# blink1mk3_003.net
KiCad netlist of a schematic drawn in EAGLE
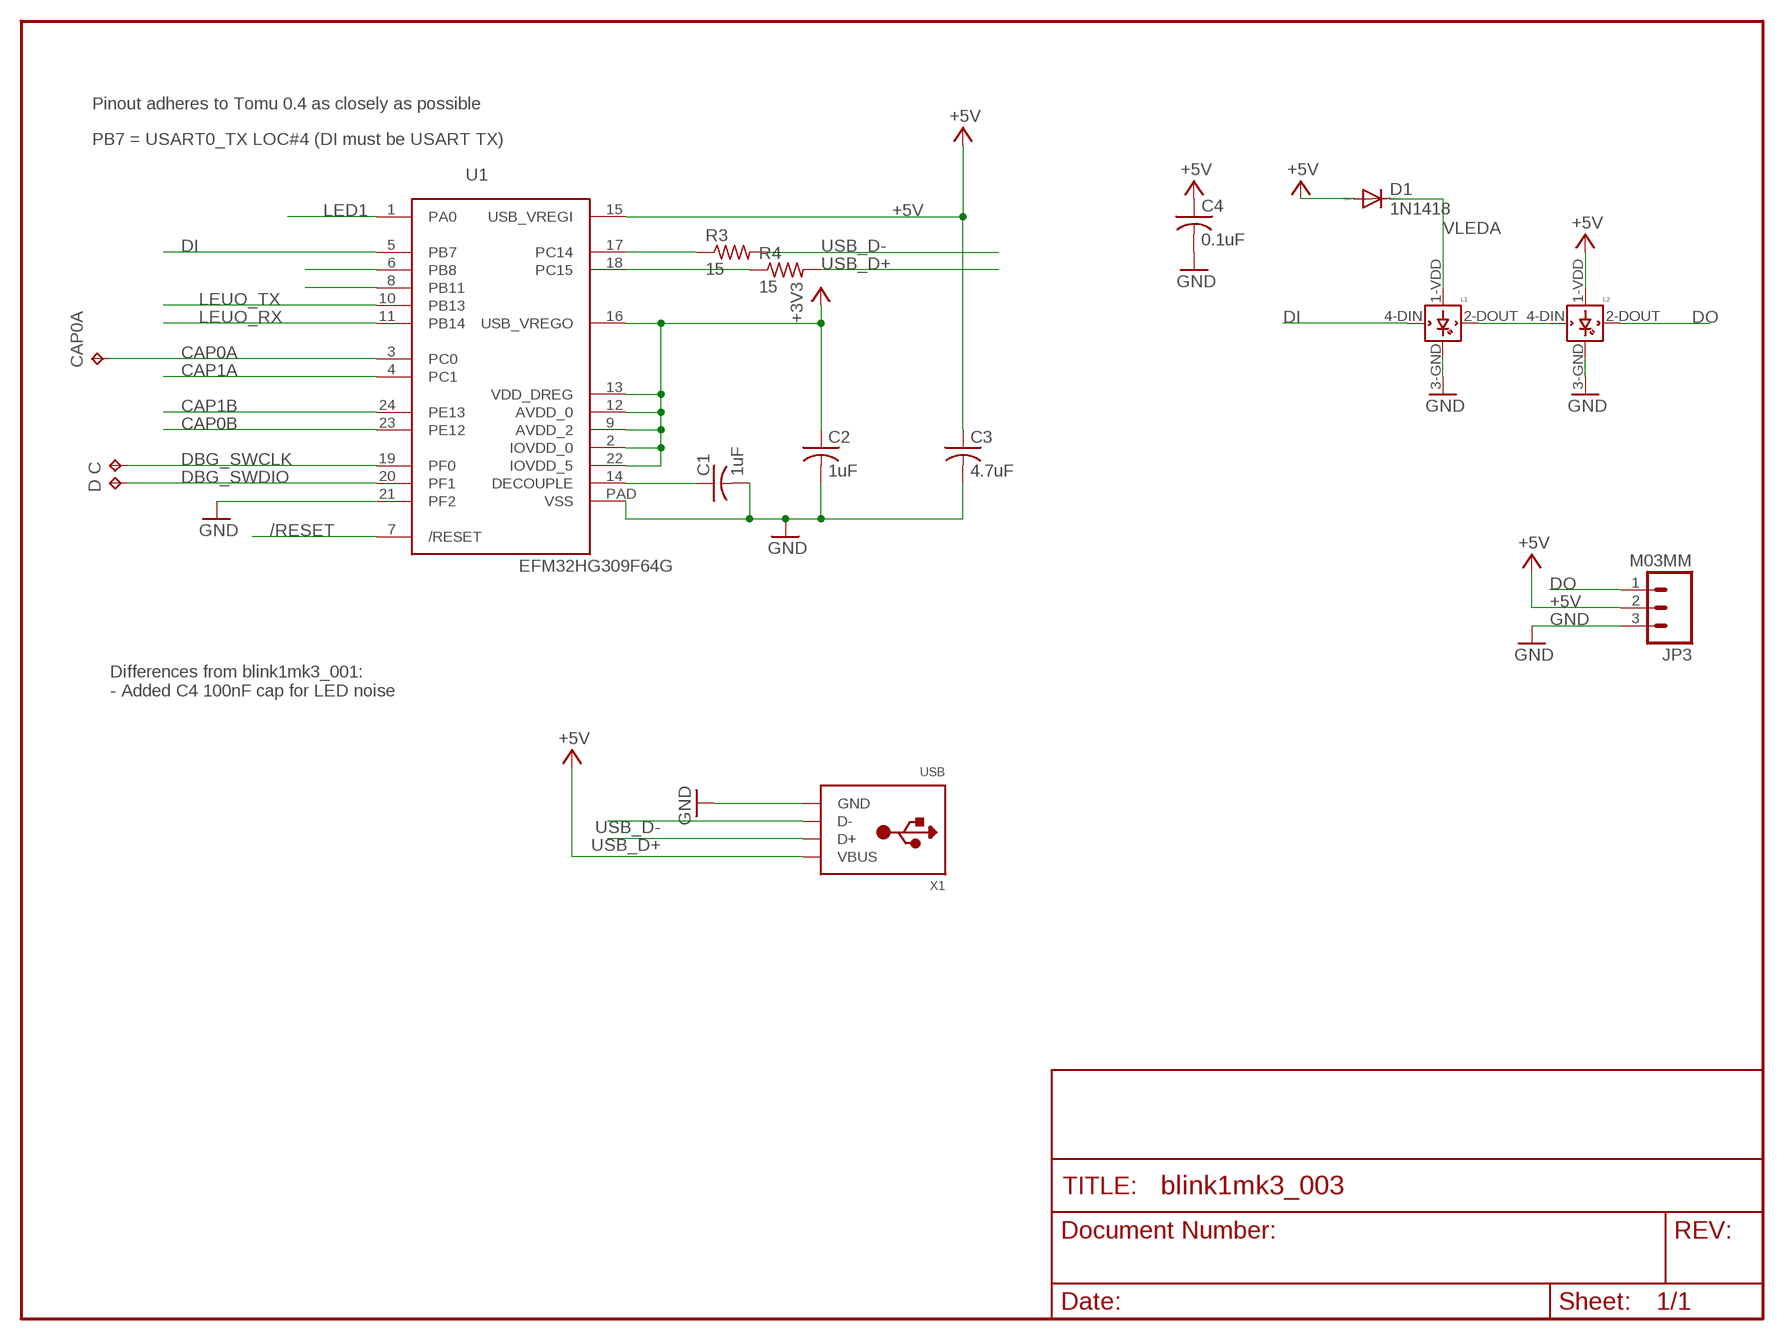
[diagram p0: schematic, sheet 1]

(export (version "E")
  (design (tool "Eeschema 10.0.6"))
  (components
    (comp (ref "C")
      (value "TPTP10R")
      (footprint "eagle-import:TP10R")
      (libsource (lib "eagle-import") (part "TPTP10R"))
    )
    (comp (ref "C1")
      (value "1uF")
      (footprint "eagle-import:C0402")
      (libsource (lib "eagle-import") (part "C-USC0402"))
    )
    (comp (ref "C2")
      (value "1uF")
      (footprint "eagle-import:C0402")
      (libsource (lib "eagle-import") (part "C-USC0402"))
    )
    (comp (ref "C3")
      (value "4.7uF")
      (footprint "eagle-import:C0402")
      (libsource (lib "eagle-import") (part "C-USC0402"))
    )
    (comp (ref "C4")
      (value "0.1uF")
      (footprint "eagle-import:C0402")
      (libsource (lib "eagle-import") (part "C-USC0402"))
    )
    (comp (ref "CAP0A")
      (value "TPTP10R")
      (footprint "eagle-import:TP10R")
      (libsource (lib "eagle-import") (part "TPTP10R"))
    )
    (comp (ref "D")
      (value "TPTP10R")
      (footprint "eagle-import:TP10R")
      (libsource (lib "eagle-import") (part "TPTP10R"))
    )
    (comp (ref "D1")
      (value "1N1418")
      (footprint "eagle-import:SOD523")
      (libsource (lib "eagle-import") (part "DIODE-SOD523"))
    )
    (comp (ref "JP3")
      (value "M03MM")
      (footprint "eagle-import:1X03-1.5MM")
      (libsource (lib "eagle-import") (part "M03MM"))
    )
    (comp (ref "L1")
      (value "WS2812B")
      (footprint "eagle-import:WS2812B")
      (libsource (lib "eagle-import") (part "WS2812B"))
    )
    (comp (ref "L2")
      (value "WS2812B")
      (footprint "eagle-import:WS2812B")
      (libsource (lib "eagle-import") (part "WS2812B"))
    )
    (comp (ref "R3")
      (value "15")
      (footprint "eagle-import:R0402")
      (libsource (lib "eagle-import") (part "R-US_R0402"))
    )
    (comp (ref "R4")
      (value "15")
      (footprint "eagle-import:R0402")
      (libsource (lib "eagle-import") (part "R-US_R0402"))
    )
    (comp (ref "U1")
      (value "EFM32HG309F64G")
      (footprint "eagle-import:QFN24PAD")
      (libsource (lib "eagle-import") (part "EFM32HG309F64G"))
    )
    (comp (ref "X1")
      (value "USB")
      (footprint "eagle-import:MOLEX-48037-1000")
      (libsource (lib "eagle-import") (part "USB"))
    )
  )
  (nets
    (net (code "1") (name "+3V3") (class "Default")
      (node (ref "C2") (pin "1") (pinfunction "1_1") (pintype "passive"))
      (node (ref "U1") (pin "12") (pinfunction "AVDD_0_12") (pintype "bidirectional"))
      (node (ref "U1") (pin "13") (pinfunction "VDD_DREG_13") (pintype "bidirectional"))
      (node (ref "U1") (pin "16") (pinfunction "USB_VREGO_16") (pintype "bidirectional"))
      (node (ref "U1") (pin "2") (pinfunction "IOVDD_0_2") (pintype "bidirectional"))
      (node (ref "U1") (pin "22") (pinfunction "IOVDD_5_22") (pintype "bidirectional"))
      (node (ref "U1") (pin "9") (pinfunction "AVDD_2_9") (pintype "bidirectional"))
    )
    (net (code "2") (name "+5V") (class "Default")
      (node (ref "C3") (pin "1") (pinfunction "1_1") (pintype "passive"))
      (node (ref "C4") (pin "1") (pinfunction "1_1") (pintype "passive"))
      (node (ref "D1") (pin "A") (pinfunction "A_A") (pintype "passive"))
      (node (ref "JP3") (pin "2") (pinfunction "2_2") (pintype "passive"))
      (node (ref "L2") (pin "1-VDD") (pinfunction "VDD_1-VDD") (pintype "bidirectional"))
      (node (ref "U1") (pin "15") (pinfunction "USB_VREGI_15") (pintype "bidirectional"))
      (node (ref "X1") (pin "1") (pinfunction "VBUS_1") (pintype "power_in"))
    )
    (net (code "3") (name "/CAP0A") (class "Default")
      (node (ref "CAP0A") (pin "TP") (pinfunction "TP_TP") (pintype "input"))
      (node (ref "U1") (pin "3") (pinfunction "PC0_3") (pintype "bidirectional"))
    )
    (net (code "4") (name "/CAP0B") (class "Default")
      (node (ref "U1") (pin "23") (pinfunction "PE12_23") (pintype "bidirectional"))
    )
    (net (code "5") (name "/CAP1A") (class "Default")
      (node (ref "U1") (pin "4") (pinfunction "PC1_4") (pintype "bidirectional"))
    )
    (net (code "6") (name "/CAP1B") (class "Default")
      (node (ref "U1") (pin "24") (pinfunction "PE13_24") (pintype "bidirectional"))
    )
    (net (code "7") (name "/DBG_SWCLK") (class "Default")
      (node (ref "C") (pin "TP") (pinfunction "TP_TP") (pintype "input"))
      (node (ref "U1") (pin "19") (pinfunction "PF0_19") (pintype "bidirectional"))
    )
    (net (code "8") (name "/DBG_SWDIO") (class "Default")
      (node (ref "D") (pin "TP") (pinfunction "TP_TP") (pintype "input"))
      (node (ref "U1") (pin "20") (pinfunction "PF1_20") (pintype "bidirectional"))
    )
    (net (code "9") (name "/DI") (class "Default")
      (node (ref "L1") (pin "4-DIN") (pinfunction "DIN_4-DIN") (pintype "input"))
      (node (ref "U1") (pin "5") (pinfunction "PB7_5") (pintype "bidirectional"))
    )
    (net (code "10") (name "/DO") (class "Default")
      (node (ref "JP3") (pin "1") (pinfunction "1_1") (pintype "passive"))
      (node (ref "L2") (pin "2-DOUT") (pinfunction "DOUT_2-DOUT") (pintype "output"))
    )
    (net (code "11") (name "/LED1") (class "Default")
      (node (ref "U1") (pin "1") (pinfunction "PA0_1") (pintype "bidirectional"))
    )
    (net (code "12") (name "/LEUO_RX") (class "Default")
      (node (ref "U1") (pin "11") (pinfunction "PB14_11") (pintype "bidirectional"))
    )
    (net (code "13") (name "/LEUO_TX") (class "Default")
      (node (ref "U1") (pin "10") (pinfunction "PB13_10") (pintype "bidirectional"))
    )
    (net (code "14") (name "/USB_D+") (class "Default")
      (node (ref "R4") (pin "2") (pinfunction "2_2") (pintype "passive"))
      (node (ref "X1") (pin "3") (pinfunction "D+_3") (pintype "bidirectional"))
    )
    (net (code "15") (name "/USB_D-") (class "Default")
      (node (ref "R3") (pin "2") (pinfunction "2_2") (pintype "passive"))
      (node (ref "X1") (pin "2") (pinfunction "D-_2") (pintype "bidirectional"))
    )
    (net (code "16") (name "/VLEDA") (class "Default")
      (node (ref "D1") (pin "C") (pinfunction "C_C") (pintype "passive"))
      (node (ref "L1") (pin "1-VDD") (pinfunction "VDD_1-VDD") (pintype "bidirectional"))
    )
    (net (code "17") (name "/{slash}RESET") (class "Default")
      (node (ref "U1") (pin "7") (pinfunction "/RESET_7") (pintype "bidirectional"))
    )
    (net (code "18") (name "GND") (class "Default")
      (node (ref "C1") (pin "2") (pinfunction "2_2") (pintype "passive"))
      (node (ref "C2") (pin "2") (pinfunction "2_2") (pintype "passive"))
      (node (ref "C3") (pin "2") (pinfunction "2_2") (pintype "passive"))
      (node (ref "C4") (pin "2") (pinfunction "2_2") (pintype "passive"))
      (node (ref "JP3") (pin "3") (pinfunction "3_3") (pintype "passive"))
      (node (ref "L1") (pin "3-GND") (pinfunction "GND_3-GND") (pintype "bidirectional"))
      (node (ref "L2") (pin "3-GND") (pinfunction "GND_3-GND") (pintype "bidirectional"))
      (node (ref "U1") (pin "21") (pinfunction "PF2_21") (pintype "bidirectional"))
      (node (ref "U1") (pin "PAD") (pinfunction "VSS_PAD") (pintype "bidirectional"))
      (node (ref "X1") (pin "4") (pinfunction "GND_4") (pintype "power_in"))
    )
    (net (code "19") (name "Net-(L1-DOUT)") (class "Default")
      (node (ref "L1") (pin "2-DOUT") (pinfunction "DOUT_2-DOUT") (pintype "output"))
      (node (ref "L2") (pin "4-DIN") (pinfunction "DIN_4-DIN") (pintype "input"))
    )
    (net (code "20") (name "Net-(U1-DECOUPLE)") (class "Default")
      (node (ref "C1") (pin "1") (pinfunction "1_1") (pintype "passive"))
      (node (ref "U1") (pin "14") (pinfunction "DECOUPLE_14") (pintype "bidirectional"))
    )
    (net (code "21") (name "Net-(U1-PC14)") (class "Default")
      (node (ref "R3") (pin "1") (pinfunction "1_1") (pintype "passive"))
      (node (ref "U1") (pin "17") (pinfunction "PC14_17") (pintype "bidirectional"))
    )
    (net (code "22") (name "Net-(U1-PC15)") (class "Default")
      (node (ref "R4") (pin "1") (pinfunction "1_1") (pintype "passive"))
      (node (ref "U1") (pin "18") (pinfunction "PC15_18") (pintype "bidirectional"))
    )
    (net (code "23") (name "unconnected-(U1-PB8-Pad6)") (class "Default")
      (node (ref "U1") (pin "6") (pinfunction "PB8_6") (pintype "bidirectional"))
    )
    (net (code "24") (name "unconnected-(U1-PB11-Pad8)") (class "Default")
      (node (ref "U1") (pin "8") (pinfunction "PB11_8") (pintype "bidirectional"))
    )
  )
)
